# PWB-MXR.net
KiCad netlist of a schematic drawn in EAGLE
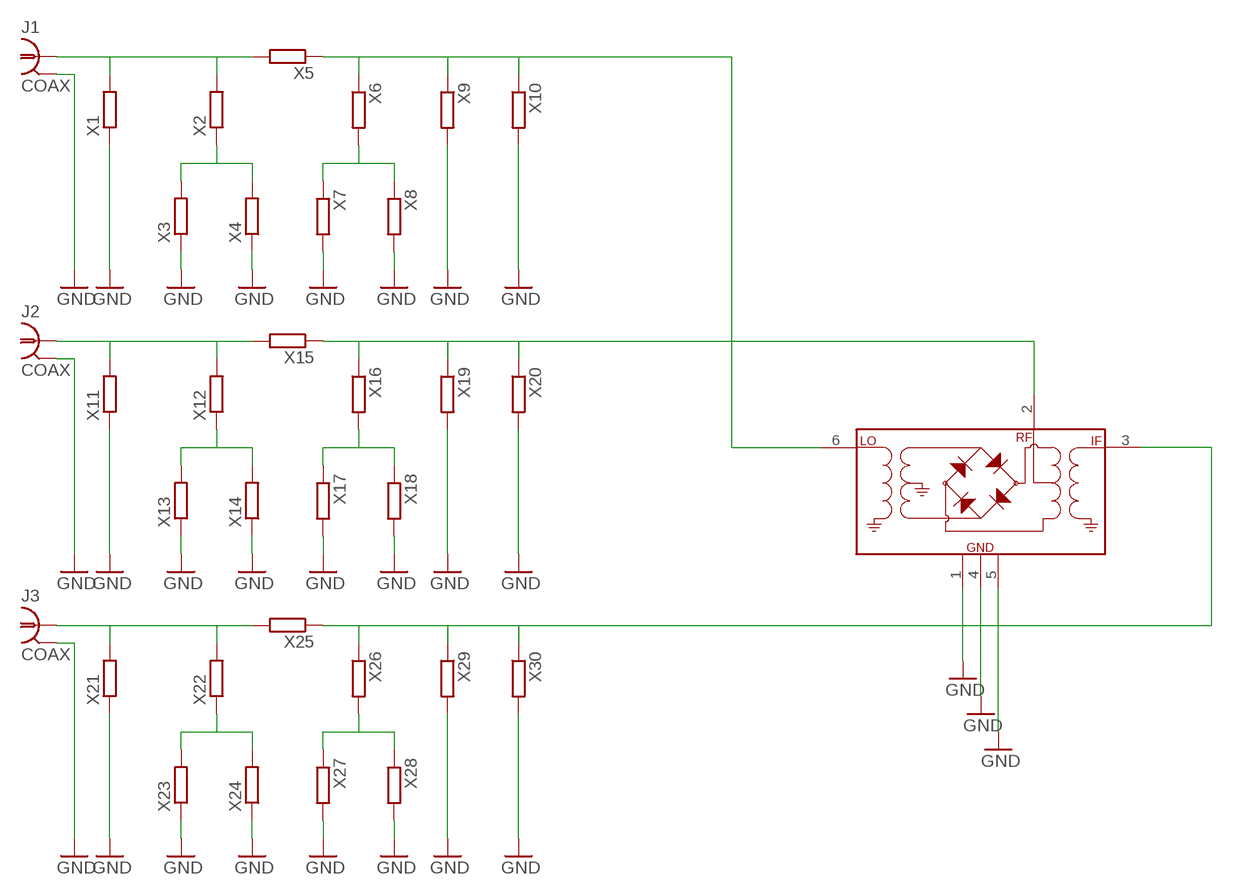
[diagram p0: schematic, sheet 1]

(export (version "E")
  (design (tool "Eeschema 10.0.6"))
  (components
    (comp (ref "J1")
      (value "COAX")
      (footprint "eagle-import:SLIM_COAX_PAD")
      (libsource (lib "eagle-import") (part "COAX"))
    )
    (comp (ref "J2")
      (value "COAX")
      (footprint "eagle-import:SLIM_COAX_PAD")
      (libsource (lib "eagle-import") (part "COAX"))
    )
    (comp (ref "J3")
      (value "COAX")
      (footprint "eagle-import:SLIM_COAX_PAD")
      (libsource (lib "eagle-import") (part "COAX"))
    )
    (comp (ref "U$1")
      (value "ADE-11X")
      (footprint "eagle-import:CD542")
      (libsource (lib "eagle-import") (part "ADE-11X"))
    )
    (comp (ref "X1")
      (value "R-EU_M0805")
      (footprint "eagle-import:M0805")
      (libsource (lib "eagle-import") (part "R-EU_M0805"))
    )
    (comp (ref "X2")
      (value "R-EU_M0805")
      (footprint "eagle-import:M0805")
      (libsource (lib "eagle-import") (part "R-EU_M0805"))
    )
    (comp (ref "X3")
      (value "R-EU_M0805")
      (footprint "eagle-import:M0805")
      (libsource (lib "eagle-import") (part "R-EU_M0805"))
    )
    (comp (ref "X4")
      (value "R-EU_M0805")
      (footprint "eagle-import:M0805")
      (libsource (lib "eagle-import") (part "R-EU_M0805"))
    )
    (comp (ref "X5")
      (value "R-EU_M0805")
      (footprint "eagle-import:M0805")
      (libsource (lib "eagle-import") (part "R-EU_M0805"))
    )
    (comp (ref "X6")
      (value "R-EU_M0805")
      (footprint "eagle-import:M0805")
      (libsource (lib "eagle-import") (part "R-EU_M0805"))
    )
    (comp (ref "X7")
      (value "R-EU_M0805")
      (footprint "eagle-import:M0805")
      (libsource (lib "eagle-import") (part "R-EU_M0805"))
    )
    (comp (ref "X8")
      (value "R-EU_M0805")
      (footprint "eagle-import:M0805")
      (libsource (lib "eagle-import") (part "R-EU_M0805"))
    )
    (comp (ref "X9")
      (value "R-EU_M0805")
      (footprint "eagle-import:M0805")
      (libsource (lib "eagle-import") (part "R-EU_M0805"))
    )
    (comp (ref "X10")
      (value "R-EU_M0805")
      (footprint "eagle-import:M0805")
      (libsource (lib "eagle-import") (part "R-EU_M0805"))
    )
    (comp (ref "X11")
      (value "R-EU_M0805")
      (footprint "eagle-import:M0805")
      (libsource (lib "eagle-import") (part "R-EU_M0805"))
    )
    (comp (ref "X12")
      (value "R-EU_M0805")
      (footprint "eagle-import:M0805")
      (libsource (lib "eagle-import") (part "R-EU_M0805"))
    )
    (comp (ref "X13")
      (value "R-EU_M0805")
      (footprint "eagle-import:M0805")
      (libsource (lib "eagle-import") (part "R-EU_M0805"))
    )
    (comp (ref "X14")
      (value "R-EU_M0805")
      (footprint "eagle-import:M0805")
      (libsource (lib "eagle-import") (part "R-EU_M0805"))
    )
    (comp (ref "X15")
      (value "R-EU_M0805")
      (footprint "eagle-import:M0805")
      (libsource (lib "eagle-import") (part "R-EU_M0805"))
    )
    (comp (ref "X16")
      (value "R-EU_M0805")
      (footprint "eagle-import:M0805")
      (libsource (lib "eagle-import") (part "R-EU_M0805"))
    )
    (comp (ref "X17")
      (value "R-EU_M0805")
      (footprint "eagle-import:M0805")
      (libsource (lib "eagle-import") (part "R-EU_M0805"))
    )
    (comp (ref "X18")
      (value "R-EU_M0805")
      (footprint "eagle-import:M0805")
      (libsource (lib "eagle-import") (part "R-EU_M0805"))
    )
    (comp (ref "X19")
      (value "R-EU_M0805")
      (footprint "eagle-import:M0805")
      (libsource (lib "eagle-import") (part "R-EU_M0805"))
    )
    (comp (ref "X20")
      (value "R-EU_M0805")
      (footprint "eagle-import:M0805")
      (libsource (lib "eagle-import") (part "R-EU_M0805"))
    )
    (comp (ref "X21")
      (value "R-EU_M0805")
      (footprint "eagle-import:M0805")
      (libsource (lib "eagle-import") (part "R-EU_M0805"))
    )
    (comp (ref "X22")
      (value "R-EU_M0805")
      (footprint "eagle-import:M0805")
      (libsource (lib "eagle-import") (part "R-EU_M0805"))
    )
    (comp (ref "X23")
      (value "R-EU_M0805")
      (footprint "eagle-import:M0805")
      (libsource (lib "eagle-import") (part "R-EU_M0805"))
    )
    (comp (ref "X24")
      (value "R-EU_M0805")
      (footprint "eagle-import:M0805")
      (libsource (lib "eagle-import") (part "R-EU_M0805"))
    )
    (comp (ref "X25")
      (value "R-EU_M0805")
      (footprint "eagle-import:M0805")
      (libsource (lib "eagle-import") (part "R-EU_M0805"))
    )
    (comp (ref "X26")
      (value "R-EU_M0805")
      (footprint "eagle-import:M0805")
      (libsource (lib "eagle-import") (part "R-EU_M0805"))
    )
    (comp (ref "X27")
      (value "R-EU_M0805")
      (footprint "eagle-import:M0805")
      (libsource (lib "eagle-import") (part "R-EU_M0805"))
    )
    (comp (ref "X28")
      (value "R-EU_M0805")
      (footprint "eagle-import:M0805")
      (libsource (lib "eagle-import") (part "R-EU_M0805"))
    )
    (comp (ref "X29")
      (value "R-EU_M0805")
      (footprint "eagle-import:M0805")
      (libsource (lib "eagle-import") (part "R-EU_M0805"))
    )
    (comp (ref "X30")
      (value "R-EU_M0805")
      (footprint "eagle-import:M0805")
      (libsource (lib "eagle-import") (part "R-EU_M0805"))
    )
  )
  (nets
    (net (code "1") (name "GND") (class "Default")
      (node (ref "J1") (pin "P$2") (pinfunction "GND_P$2") (pintype "power_in"))
      (node (ref "J2") (pin "P$2") (pinfunction "GND_P$2") (pintype "power_in"))
      (node (ref "J3") (pin "P$2") (pinfunction "GND_P$2") (pintype "power_in"))
      (node (ref "U$1") (pin "1") (pinfunction "GND_1") (pintype "bidirectional"))
      (node (ref "U$1") (pin "4") (pinfunction "GND_4") (pintype "bidirectional"))
      (node (ref "U$1") (pin "5") (pinfunction "GND_5") (pintype "bidirectional"))
      (node (ref "X1") (pin "1") (pinfunction "1_1") (pintype "passive"))
      (node (ref "X10") (pin "2") (pinfunction "2_2") (pintype "passive"))
      (node (ref "X11") (pin "1") (pinfunction "1_1") (pintype "passive"))
      (node (ref "X13") (pin "1") (pinfunction "1_1") (pintype "passive"))
      (node (ref "X14") (pin "1") (pinfunction "1_1") (pintype "passive"))
      (node (ref "X17") (pin "2") (pinfunction "2_2") (pintype "passive"))
      (node (ref "X18") (pin "2") (pinfunction "2_2") (pintype "passive"))
      (node (ref "X19") (pin "2") (pinfunction "2_2") (pintype "passive"))
      (node (ref "X20") (pin "2") (pinfunction "2_2") (pintype "passive"))
      (node (ref "X21") (pin "1") (pinfunction "1_1") (pintype "passive"))
      (node (ref "X23") (pin "1") (pinfunction "1_1") (pintype "passive"))
      (node (ref "X24") (pin "1") (pinfunction "1_1") (pintype "passive"))
      (node (ref "X27") (pin "2") (pinfunction "2_2") (pintype "passive"))
      (node (ref "X28") (pin "2") (pinfunction "2_2") (pintype "passive"))
      (node (ref "X29") (pin "2") (pinfunction "2_2") (pintype "passive"))
      (node (ref "X3") (pin "1") (pinfunction "1_1") (pintype "passive"))
      (node (ref "X30") (pin "2") (pinfunction "2_2") (pintype "passive"))
      (node (ref "X4") (pin "1") (pinfunction "1_1") (pintype "passive"))
      (node (ref "X7") (pin "2") (pinfunction "2_2") (pintype "passive"))
      (node (ref "X8") (pin "2") (pinfunction "2_2") (pintype "passive"))
      (node (ref "X9") (pin "2") (pinfunction "2_2") (pintype "passive"))
    )
    (net (code "2") (name "Net-(J1-1)") (class "Default")
      (node (ref "J1") (pin "P$1") (pinfunction "1_P$1") (pintype "passive"))
      (node (ref "X1") (pin "2") (pinfunction "2_2") (pintype "passive"))
      (node (ref "X2") (pin "2") (pinfunction "2_2") (pintype "passive"))
      (node (ref "X5") (pin "2") (pinfunction "2_2") (pintype "passive"))
    )
    (net (code "3") (name "Net-(J2-1)") (class "Default")
      (node (ref "J2") (pin "P$1") (pinfunction "1_P$1") (pintype "passive"))
      (node (ref "X11") (pin "2") (pinfunction "2_2") (pintype "passive"))
      (node (ref "X12") (pin "2") (pinfunction "2_2") (pintype "passive"))
      (node (ref "X15") (pin "2") (pinfunction "2_2") (pintype "passive"))
    )
    (net (code "4") (name "Net-(J3-1)") (class "Default")
      (node (ref "J3") (pin "P$1") (pinfunction "1_P$1") (pintype "passive"))
      (node (ref "X21") (pin "2") (pinfunction "2_2") (pintype "passive"))
      (node (ref "X22") (pin "2") (pinfunction "2_2") (pintype "passive"))
      (node (ref "X25") (pin "2") (pinfunction "2_2") (pintype "passive"))
    )
    (net (code "5") (name "Net-(U$1-IF)") (class "Default")
      (node (ref "U$1") (pin "3") (pinfunction "IF_3") (pintype "bidirectional"))
      (node (ref "X25") (pin "1") (pinfunction "1_1") (pintype "passive"))
      (node (ref "X26") (pin "1") (pinfunction "1_1") (pintype "passive"))
      (node (ref "X29") (pin "1") (pinfunction "1_1") (pintype "passive"))
      (node (ref "X30") (pin "1") (pinfunction "1_1") (pintype "passive"))
    )
    (net (code "6") (name "Net-(U$1-LO)") (class "Default")
      (node (ref "U$1") (pin "6") (pinfunction "LO_6") (pintype "bidirectional"))
      (node (ref "X10") (pin "1") (pinfunction "1_1") (pintype "passive"))
      (node (ref "X5") (pin "1") (pinfunction "1_1") (pintype "passive"))
      (node (ref "X6") (pin "1") (pinfunction "1_1") (pintype "passive"))
      (node (ref "X9") (pin "1") (pinfunction "1_1") (pintype "passive"))
    )
    (net (code "7") (name "Net-(U$1-RF)") (class "Default")
      (node (ref "U$1") (pin "2") (pinfunction "RF_2") (pintype "bidirectional"))
      (node (ref "X15") (pin "1") (pinfunction "1_1") (pintype "passive"))
      (node (ref "X16") (pin "1") (pinfunction "1_1") (pintype "passive"))
      (node (ref "X19") (pin "1") (pinfunction "1_1") (pintype "passive"))
      (node (ref "X20") (pin "1") (pinfunction "1_1") (pintype "passive"))
    )
    (net (code "8") (name "Net-(X2-Pad1)") (class "Default")
      (node (ref "X2") (pin "1") (pinfunction "1_1") (pintype "passive"))
      (node (ref "X3") (pin "2") (pinfunction "2_2") (pintype "passive"))
      (node (ref "X4") (pin "2") (pinfunction "2_2") (pintype "passive"))
    )
    (net (code "9") (name "Net-(X6-Pad2)") (class "Default")
      (node (ref "X6") (pin "2") (pinfunction "2_2") (pintype "passive"))
      (node (ref "X7") (pin "1") (pinfunction "1_1") (pintype "passive"))
      (node (ref "X8") (pin "1") (pinfunction "1_1") (pintype "passive"))
    )
    (net (code "10") (name "Net-(X12-Pad1)") (class "Default")
      (node (ref "X12") (pin "1") (pinfunction "1_1") (pintype "passive"))
      (node (ref "X13") (pin "2") (pinfunction "2_2") (pintype "passive"))
      (node (ref "X14") (pin "2") (pinfunction "2_2") (pintype "passive"))
    )
    (net (code "11") (name "Net-(X16-Pad2)") (class "Default")
      (node (ref "X16") (pin "2") (pinfunction "2_2") (pintype "passive"))
      (node (ref "X17") (pin "1") (pinfunction "1_1") (pintype "passive"))
      (node (ref "X18") (pin "1") (pinfunction "1_1") (pintype "passive"))
    )
    (net (code "12") (name "Net-(X22-Pad1)") (class "Default")
      (node (ref "X22") (pin "1") (pinfunction "1_1") (pintype "passive"))
      (node (ref "X23") (pin "2") (pinfunction "2_2") (pintype "passive"))
      (node (ref "X24") (pin "2") (pinfunction "2_2") (pintype "passive"))
    )
    (net (code "13") (name "Net-(X26-Pad2)") (class "Default")
      (node (ref "X26") (pin "2") (pinfunction "2_2") (pintype "passive"))
      (node (ref "X27") (pin "1") (pinfunction "1_1") (pintype "passive"))
      (node (ref "X28") (pin "1") (pinfunction "1_1") (pintype "passive"))
    )
  )
)
